# v1_1.net
KiCad netlist of a schematic drawn in EasyEDA Pro
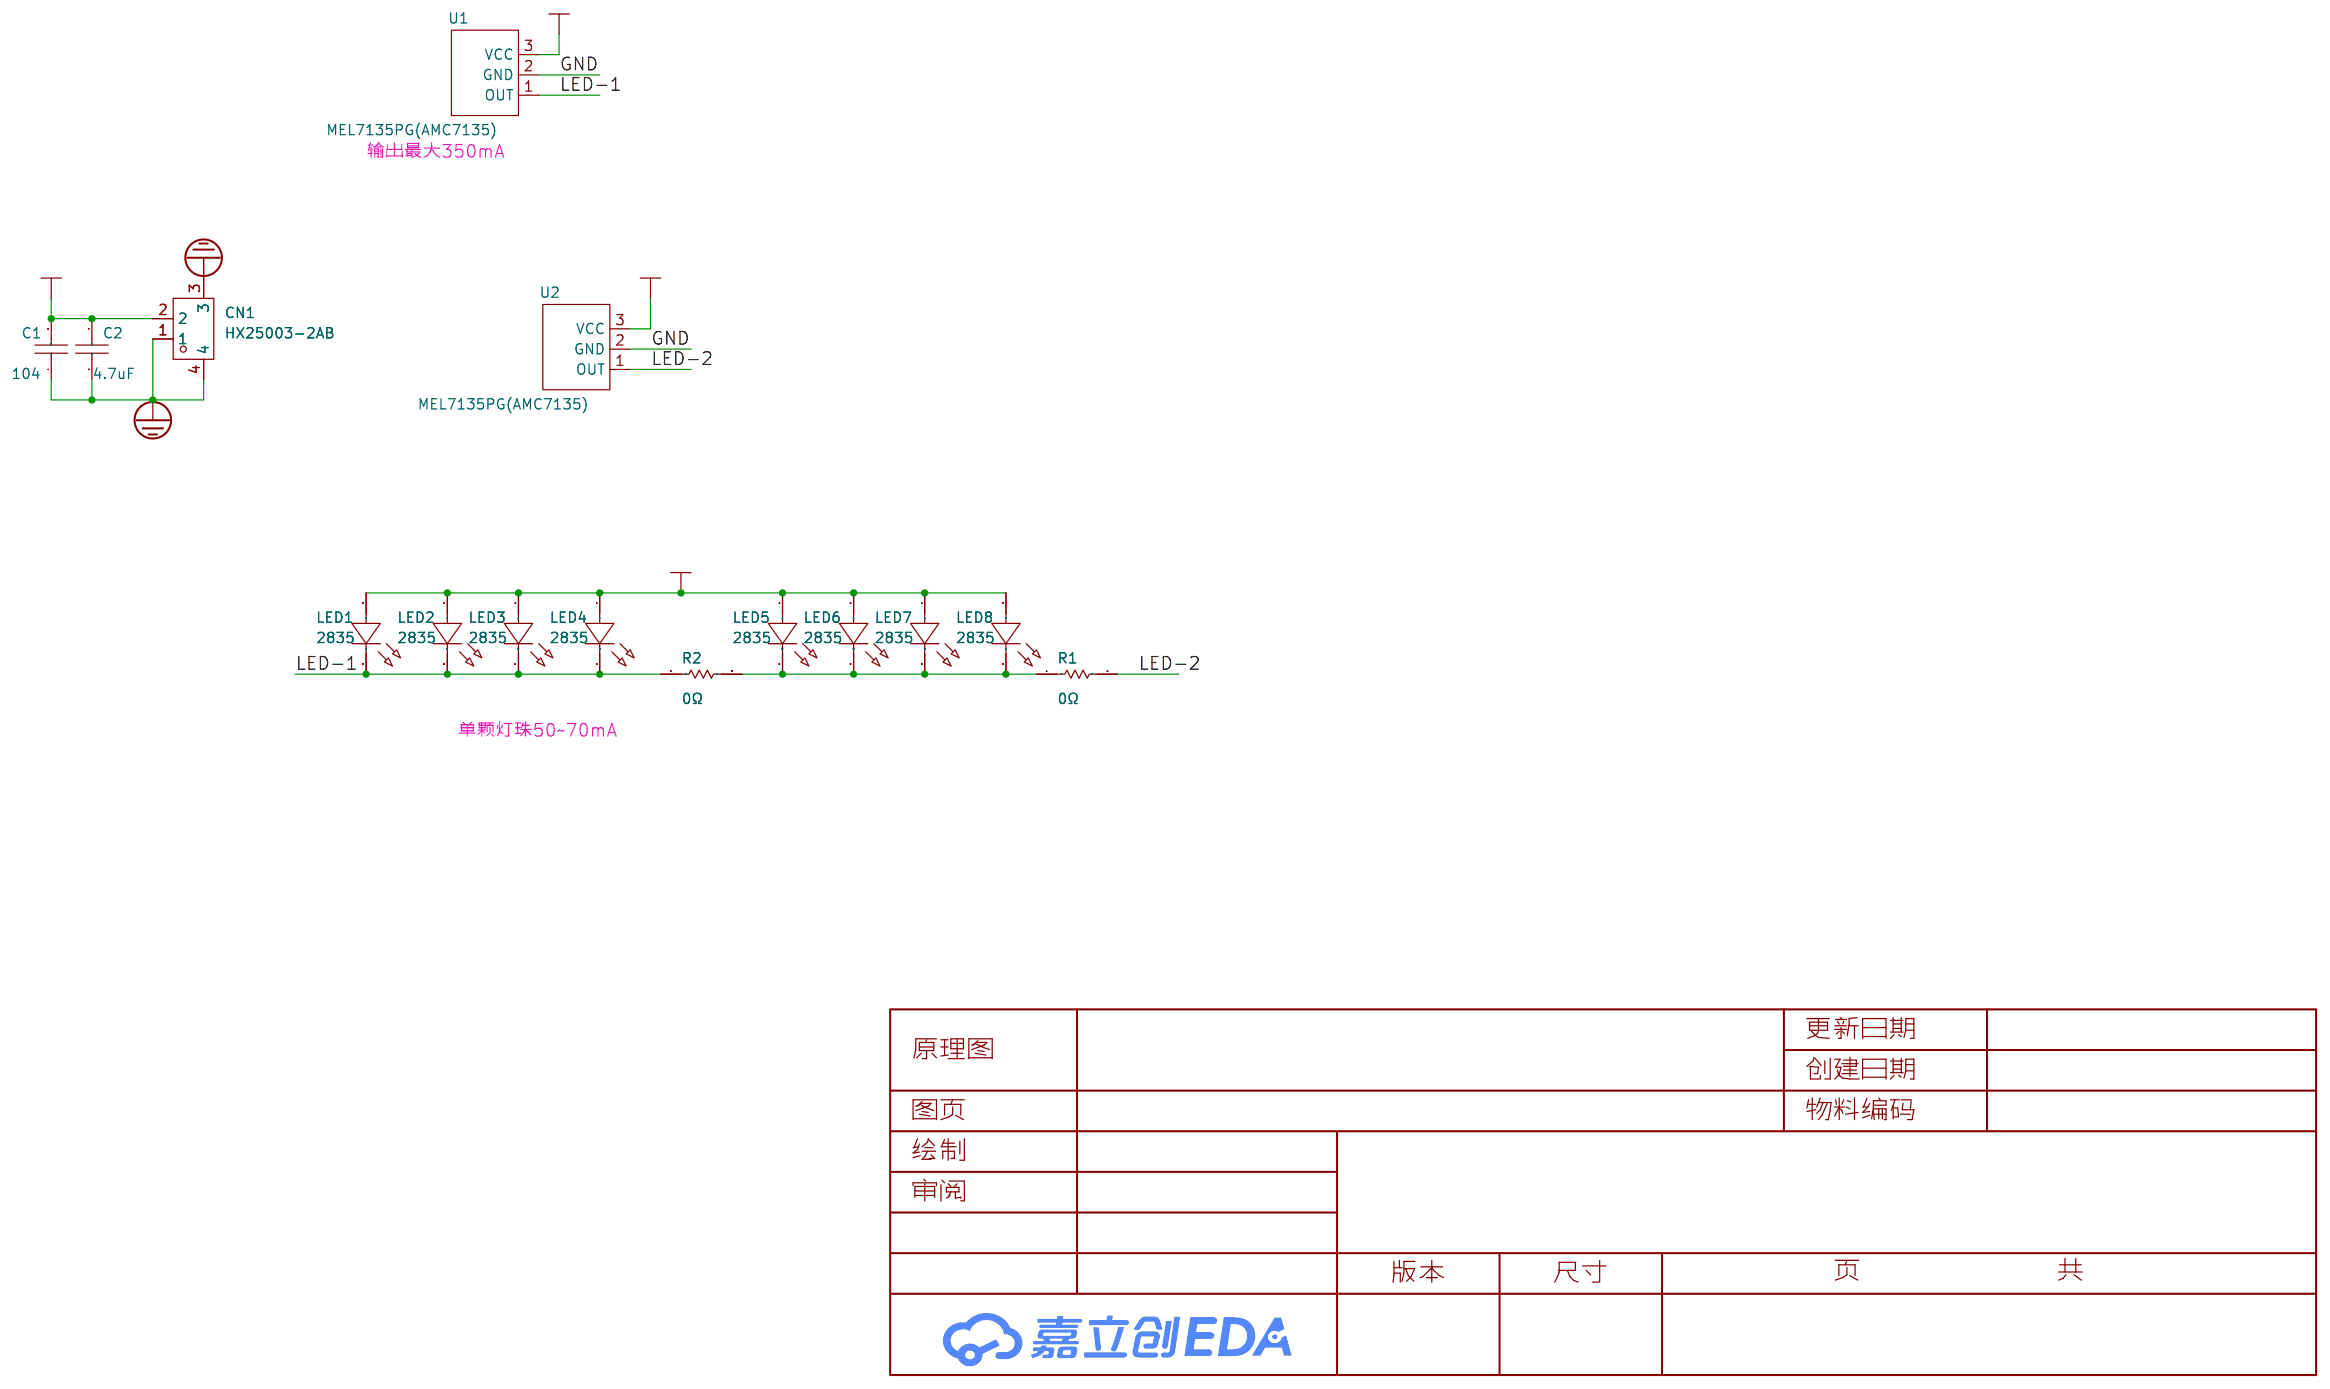
[diagram p0: schematic sheet]

(export (version "E")
  (design (tool "Eeschema 10.0.6"))
  (components
    (comp (ref "C1")
      (value "104")
      (footprint "easyedapro:0603C")
      (description "Capacitor (Semiconductor SIM Model)")
      (libsource (lib "easyedapro") (part "Cap Semi"))
    )
    (comp (ref "C2") (value "4.7uF") (libsource (lib "easyedapro") (part "CAP")))
    (comp (ref "CN1")
      (value "HX25003-2AB")
      (footprint "easyedapro:CONN-SMD_P2.50_HX25003-2AB")
      (fields (field (name "Manufacturer") "HX(红星)"))
      (libsource (lib "easyedapro") (part "HX25003-2AB"))
    )
    (comp (ref "LED1")
      (value "2835")
      (footprint "easyedapro:LED-SMD_L3.5-W2.8_2835")
      (libsource (lib "easyedapro") (part "2835"))
    )
    (comp (ref "LED2")
      (value "2835")
      (footprint "easyedapro:LED-SMD_L3.5-W2.8_2835")
      (libsource (lib "easyedapro") (part "2835"))
    )
    (comp (ref "LED3")
      (value "2835")
      (footprint "easyedapro:LED-SMD_L3.5-W2.8_2835")
      (libsource (lib "easyedapro") (part "2835"))
    )
    (comp (ref "LED4")
      (value "2835")
      (footprint "easyedapro:LED-SMD_L3.5-W2.8_2835")
      (libsource (lib "easyedapro") (part "2835"))
    )
    (comp (ref "LED5")
      (value "2835")
      (footprint "easyedapro:LED-SMD_L3.5-W2.8_2835")
      (libsource (lib "easyedapro") (part "2835"))
    )
    (comp (ref "LED6")
      (value "2835")
      (footprint "easyedapro:LED-SMD_L3.5-W2.8_2835")
      (libsource (lib "easyedapro") (part "2835"))
    )
    (comp (ref "LED7")
      (value "2835")
      (footprint "easyedapro:LED-SMD_L3.5-W2.8_2835")
      (libsource (lib "easyedapro") (part "2835"))
    )
    (comp (ref "LED8")
      (value "2835")
      (footprint "easyedapro:LED-SMD_L3.5-W2.8_2835")
      (libsource (lib "easyedapro") (part "2835"))
    )
    (comp (ref "R1")
      (value "0Ω")
      (footprint "easyedapro:10")
      (description "Resistor")
      (libsource (lib "easyedapro") (part "RES"))
    )
    (comp (ref "R2")
      (value "0Ω")
      (footprint "easyedapro:10")
      (description "Resistor")
      (libsource (lib "easyedapro") (part "RES"))
    )
    (comp (ref "U1")
      (value "MEL7135PG(AMC7135)")
      (footprint "easyedapro:SOT-89-3_L4.5-W2.5-P1.50-LS4.2-BR")
      (description "类型:-;工作电压(DC):2.7V~6V;开关频率:-;通道数:1;输出电压:-;输出电流:350mA;调光:-;拓扑结构:-;")
      (fields (field (name "Manufacturer") "MICRONE(南京微盟)"))
      (libsource (lib "easyedapro") (part "MEL7135PG"))
    )
    (comp (ref "U2")
      (value "MEL7135PG(AMC7135)")
      (footprint "easyedapro:SOT-89-3_L4.5-W2.5-P1.50-LS4.2-BR")
      (description "类型:-;工作电压(DC):2.7V~6V;开关频率:-;通道数:1;输出电压:-;输出电流:350mA;调光:-;拓扑结构:-;")
      (fields (field (name "Manufacturer") "MICRONE(南京微盟)"))
      (libsource (lib "easyedapro") (part "MEL7135PG"))
    )
  )
  (nets
    (net (code "1") (name "/LED-1") (class "Default")
      (node (ref "LED1") (pin "2") (pinfunction "C_2") (pintype "unspecified"))
      (node (ref "LED2") (pin "2") (pinfunction "C_2") (pintype "unspecified"))
      (node (ref "LED3") (pin "2") (pinfunction "C_2") (pintype "unspecified"))
      (node (ref "LED4") (pin "2") (pinfunction "C_2") (pintype "unspecified"))
      (node (ref "R2") (pin "1") (pinfunction "1_1") (pintype "unspecified"))
      (node (ref "U1") (pin "1") (pinfunction "OUT_1") (pintype "unspecified"))
    )
    (net (code "2") (name "/LED-2") (class "Default")
      (node (ref "R1") (pin "2") (pinfunction "2_2") (pintype "unspecified"))
      (node (ref "U2") (pin "1") (pinfunction "OUT_1") (pintype "unspecified"))
    )
    (net (code "3") (name "5V_VCC") (class "Default")
      (node (ref "C1") (pin "2") (pinfunction "2_2") (pintype "unspecified"))
      (node (ref "C2") (pin "1") (pinfunction "1_1") (pintype "input"))
      (node (ref "CN1") (pin "2") (pinfunction "2_2") (pintype "unspecified"))
      (node (ref "LED1") (pin "1") (pinfunction "A_1") (pintype "unspecified"))
      (node (ref "LED2") (pin "1") (pinfunction "A_1") (pintype "unspecified"))
      (node (ref "LED3") (pin "1") (pinfunction "A_1") (pintype "unspecified"))
      (node (ref "LED4") (pin "1") (pinfunction "A_1") (pintype "unspecified"))
      (node (ref "LED5") (pin "1") (pinfunction "A_1") (pintype "unspecified"))
      (node (ref "LED6") (pin "1") (pinfunction "A_1") (pintype "unspecified"))
      (node (ref "LED7") (pin "1") (pinfunction "A_1") (pintype "unspecified"))
      (node (ref "LED8") (pin "1") (pinfunction "A_1") (pintype "unspecified"))
      (node (ref "U1") (pin "3") (pinfunction "VCC_3") (pintype "unspecified"))
      (node (ref "U2") (pin "3") (pinfunction "VCC_3") (pintype "unspecified"))
    )
    (net (code "4") (name "GND") (class "Default")
      (node (ref "C1") (pin "1") (pinfunction "1_1") (pintype "unspecified"))
      (node (ref "C2") (pin "2") (pinfunction "2_2") (pintype "input"))
      (node (ref "CN1") (pin "1") (pinfunction "1_1") (pintype "unspecified"))
      (node (ref "CN1") (pin "3") (pinfunction "3_3") (pintype "unspecified"))
      (node (ref "CN1") (pin "4") (pinfunction "4_4") (pintype "unspecified"))
      (node (ref "U1") (pin "2") (pinfunction "GND_2") (pintype "unspecified"))
      (node (ref "U2") (pin "2") (pinfunction "GND_2") (pintype "unspecified"))
    )
    (net (code "5") (name "Net-(LED5-C)") (class "Default")
      (node (ref "LED5") (pin "2") (pinfunction "C_2") (pintype "unspecified"))
      (node (ref "LED6") (pin "2") (pinfunction "C_2") (pintype "unspecified"))
      (node (ref "LED7") (pin "2") (pinfunction "C_2") (pintype "unspecified"))
      (node (ref "LED8") (pin "2") (pinfunction "C_2") (pintype "unspecified"))
      (node (ref "R1") (pin "1") (pinfunction "1_1") (pintype "unspecified"))
      (node (ref "R2") (pin "2") (pinfunction "2_2") (pintype "unspecified"))
    )
  )
)
